# SCH_Forhorse_acw02_esphome_v2_2026-06-07.net
KiCad netlist of a schematic drawn in EasyEDA
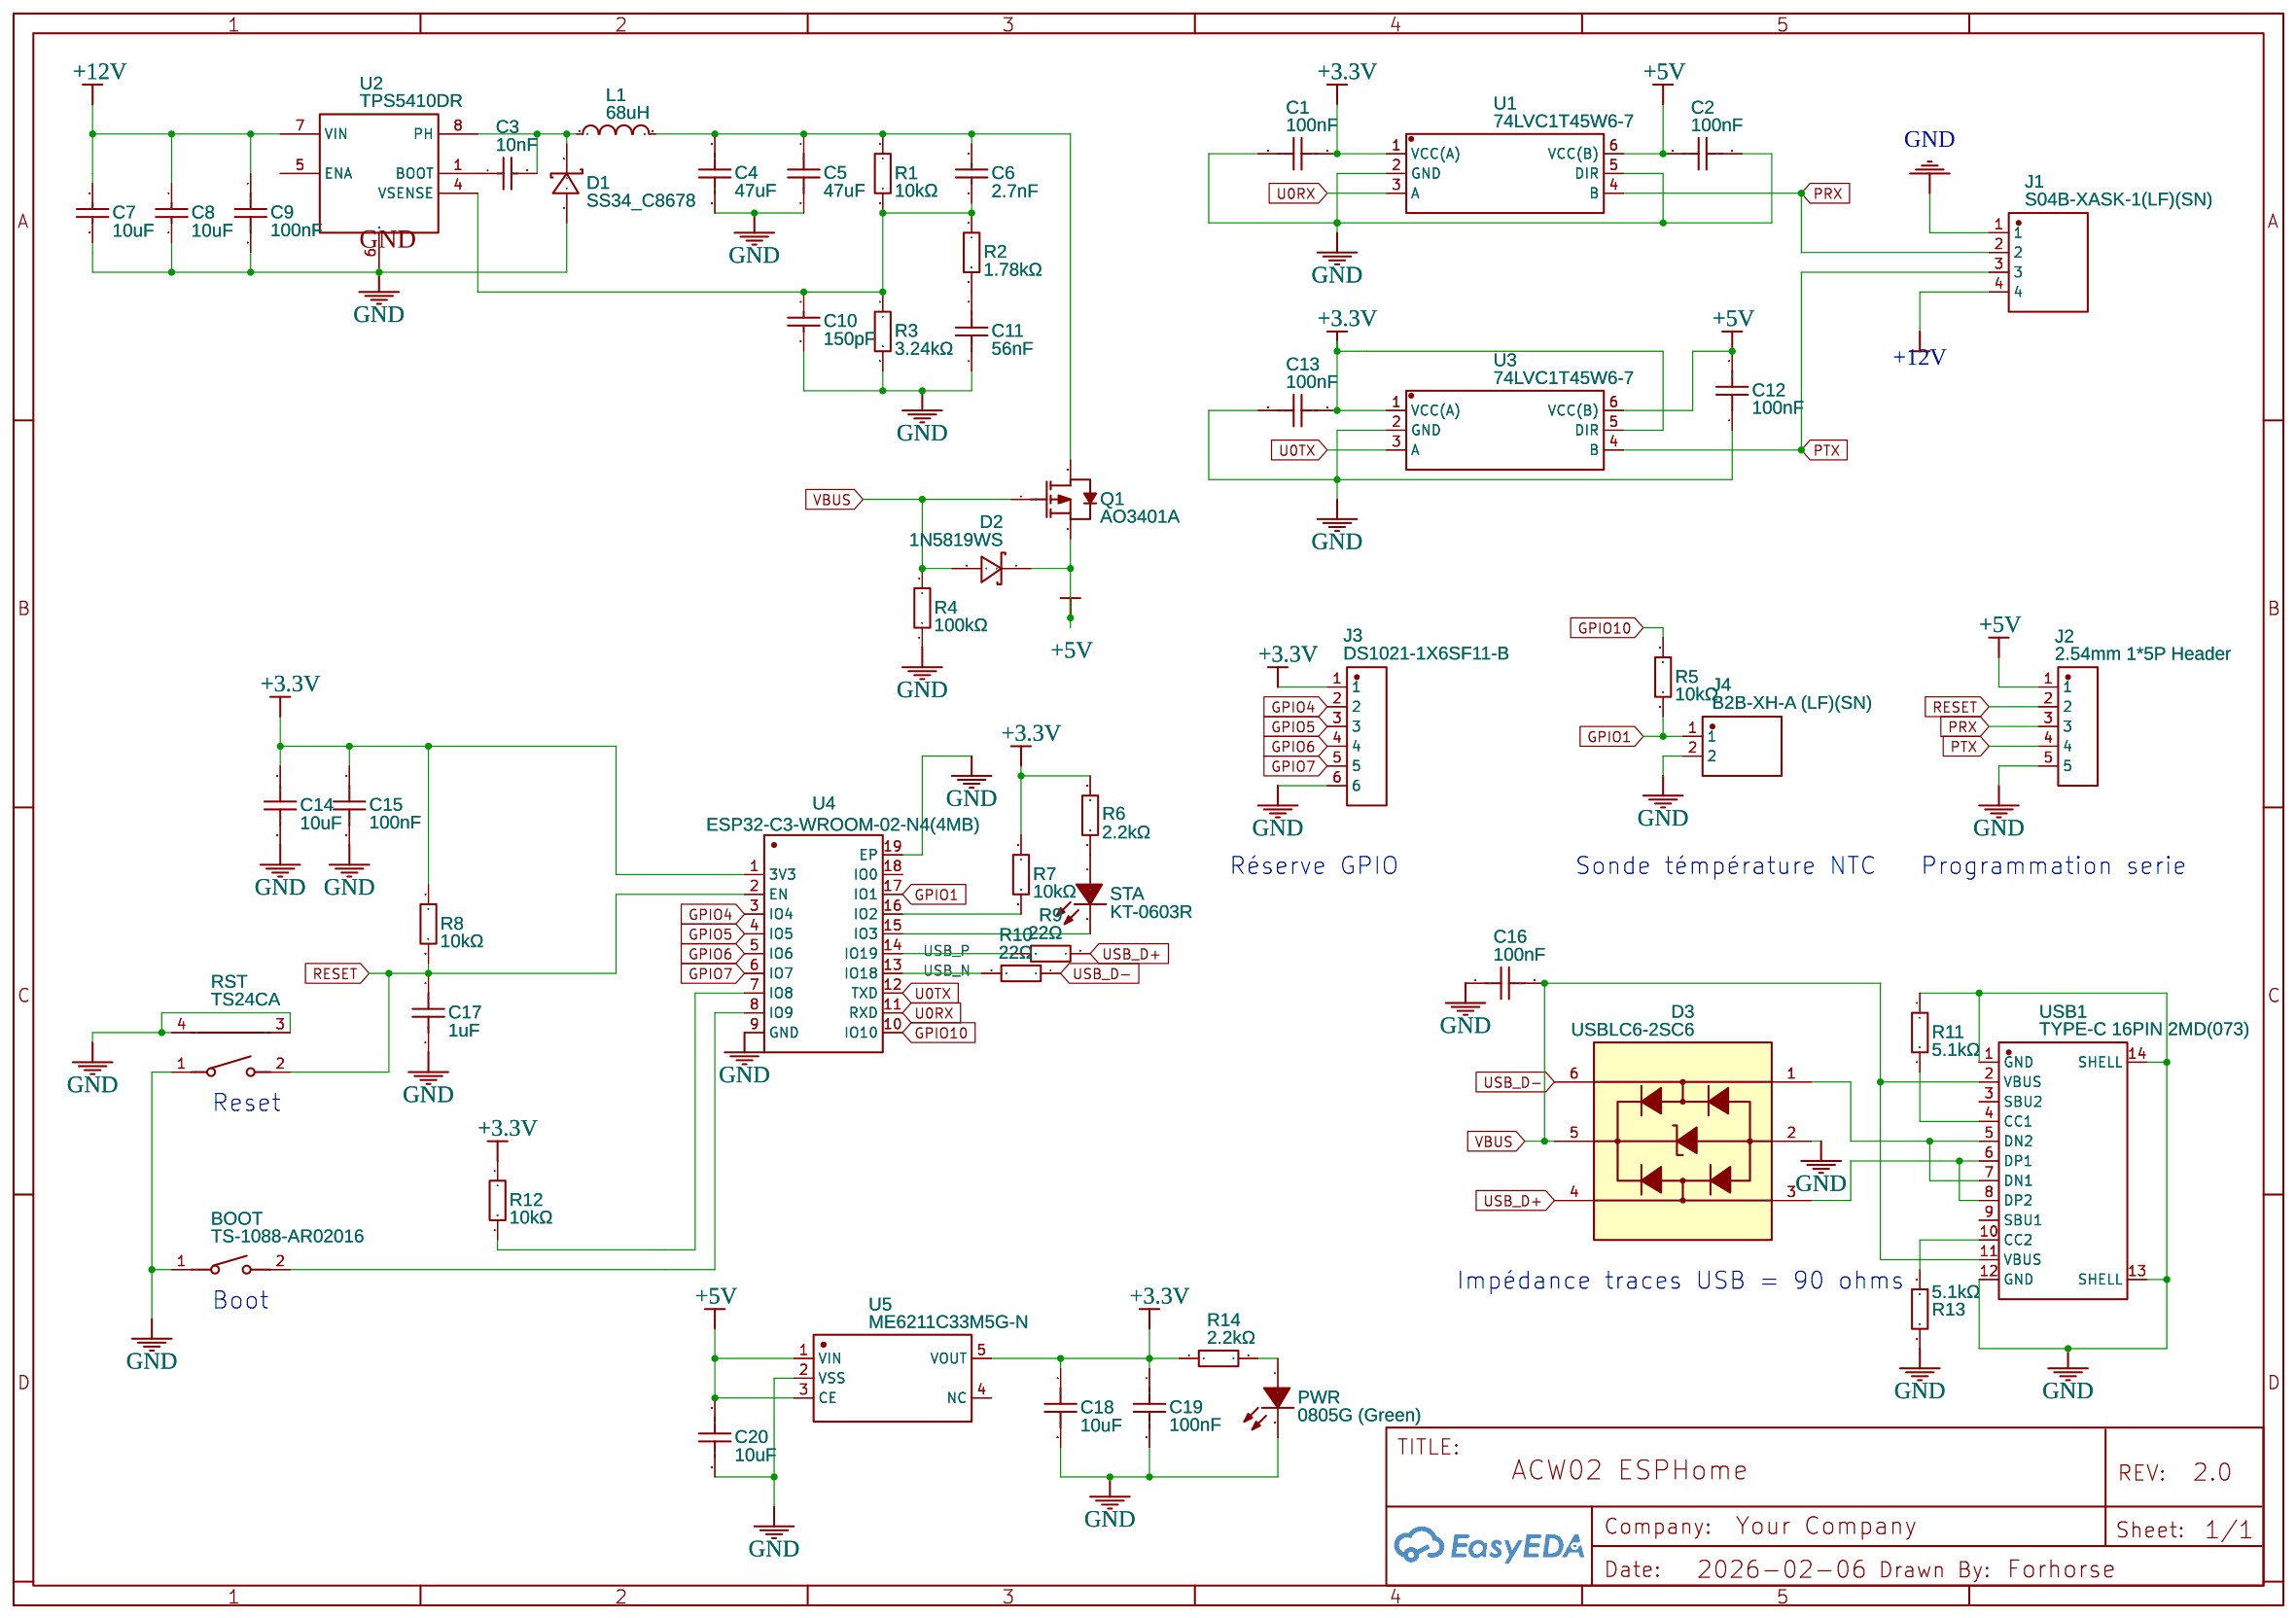
[diagram p0: schematic sheet]

(export (version "E")
  (design (tool "Eeschema 10.0.6"))
  (components
    (comp (ref "BOOT")
      (value "TS-1088-AR02016")
      (fields (field (name "Manufacturer") "XUNPU(讯普)"))
      (libsource (lib "") (part "TS-1088-AR02016"))
    )
    (comp (ref "C1")
      (value "100nF")
      (fields
        (field (name "Manufacturer Part") "CL05B104KO5NNNC")
        (field (name "Manufacturer") "SAMSUNG(三星)")
      )
      (libsource (lib "") (part "CL05B104KO5NNNC_1"))
    )
    (comp (ref "C2")
      (value "100nF")
      (fields
        (field (name "Manufacturer Part") "CL05B104KO5NNNC")
        (field (name "Manufacturer") "SAMSUNG(三星)")
      )
      (libsource (lib "") (part "CL05B104KO5NNNC_1"))
    )
    (comp (ref "C3")
      (value "10nF")
      (fields (field (name "Manufacturer Part") "0603B103K500NT") (field (name "Manufacturer") "FH(风华)"))
      (libsource (lib "") (part "0603B103K500NT"))
    )
    (comp (ref "C4")
      (value "47uF")
      (fields
        (field (name "Manufacturer Part") "CL31A476MPHNNNE")
        (field (name "Manufacturer") "SAMSUNG(三星)")
      )
      (libsource (lib "") (part "CL31A476MPHNNNE"))
    )
    (comp (ref "C5")
      (value "47uF")
      (fields
        (field (name "Manufacturer Part") "CL31A476MPHNNNE")
        (field (name "Manufacturer") "SAMSUNG(三星)")
      )
      (libsource (lib "") (part "CL31A476MPHNNNE"))
    )
    (comp (ref "C6")
      (value "2.7nF")
      (fields
        (field (name "Manufacturer Part") "GRM1885C1H272JA01D")
        (field (name "Manufacturer") "muRata(村田)")
      )
      (libsource (lib "") (part "GRM1885C1H272JA01D"))
    )
    (comp (ref "C7")
      (value "10uF")
      (fields
        (field (name "Manufacturer Part") "CL31A106KBHNNNE")
        (field (name "Manufacturer") "SAMSUNG(三星)")
      )
      (libsource (lib "") (part "CL31A106KBHNNNE"))
    )
    (comp (ref "C8")
      (value "10uF")
      (fields
        (field (name "Manufacturer Part") "CL31A106KBHNNNE")
        (field (name "Manufacturer") "SAMSUNG(三星)")
      )
      (libsource (lib "") (part "CL31A106KBHNNNE"))
    )
    (comp (ref "C9")
      (value "100nF")
      (fields
        (field (name "Manufacturer Part") "CL05B104KB54PNC")
        (field (name "Manufacturer") "SAMSUNG(三星)")
      )
      (libsource (lib "") (part "CL05B104KB54PNC"))
    )
    (comp (ref "C10")
      (value "150pF")
      (fields (field (name "Manufacturer Part") "0603B151K500NT") (field (name "Manufacturer") "FH(风华)"))
      (libsource (lib "") (part "0603B151K500NT"))
    )
    (comp (ref "C11")
      (value "56nF")
      (fields
        (field (name "Manufacturer Part") "CC0603KRX7R9BB563")
        (field (name "Manufacturer") "YAGEO(国巨)")
      )
      (libsource (lib "") (part "CC0603KRX7R9BB563"))
    )
    (comp (ref "C12")
      (value "100nF")
      (fields
        (field (name "Manufacturer Part") "CL05B104KO5NNNC")
        (field (name "Manufacturer") "SAMSUNG(三星)")
      )
      (libsource (lib "") (part "CL05B104KO5NNNC_2"))
    )
    (comp (ref "C13")
      (value "100nF")
      (fields
        (field (name "Manufacturer Part") "CL05B104KO5NNNC")
        (field (name "Manufacturer") "SAMSUNG(三星)")
      )
      (libsource (lib "") (part "CL05B104KO5NNNC_1"))
    )
    (comp (ref "C14")
      (value "10uF")
      (fields
        (field (name "Manufacturer Part") "CL10A106KP8NNNC")
        (field (name "Manufacturer") "SAMSUNG(三星)")
      )
      (libsource (lib "") (part "CL10A106KP8NNNC"))
    )
    (comp (ref "C15")
      (value "100nF")
      (fields
        (field (name "Manufacturer Part") "CL05B104KO5NNNC")
        (field (name "Manufacturer") "SAMSUNG(三星)")
      )
      (libsource (lib "") (part "CL05B104KO5NNNC"))
    )
    (comp (ref "C16")
      (value "100nF")
      (fields
        (field (name "Manufacturer Part") "CL05B104KO5NNNC")
        (field (name "Manufacturer") "SAMSUNG(三星)")
      )
      (libsource (lib "") (part "CL05B104KO5NNNC_3"))
    )
    (comp (ref "C17")
      (value "1uF")
      (fields
        (field (name "Manufacturer Part") "CL10A105KB8NNNC")
        (field (name "Manufacturer") "SAMSUNG(三星)")
      )
      (libsource (lib "") (part "CL10A105KB8NNNC"))
    )
    (comp (ref "C18")
      (value "10uF")
      (fields
        (field (name "Manufacturer Part") "CL10A106KP8NNNC")
        (field (name "Manufacturer") "SAMSUNG(三星)")
      )
      (libsource (lib "") (part "CL10A106KP8NNNC"))
    )
    (comp (ref "C19")
      (value "100nF")
      (fields
        (field (name "Manufacturer Part") "CL05B104KO5NNNC")
        (field (name "Manufacturer") "SAMSUNG(三星)")
      )
      (libsource (lib "") (part "CL05B104KO5NNNC"))
    )
    (comp (ref "C20")
      (value "10uF")
      (fields
        (field (name "Manufacturer Part") "CL10A106KP8NNNC")
        (field (name "Manufacturer") "SAMSUNG(三星)")
      )
      (libsource (lib "") (part "CL10A106KP8NNNC"))
    )
    (comp (ref "D1")
      (value "SS34_C8678")
      (fields (field (name "Manufacturer Part") "SS34") (field (name "Manufacturer") "MDD(辰达半导体)"))
      (libsource (lib "") (part "SS34_C8678"))
    )
    (comp (ref "D2")
      (value "1N5819WS")
      (fields (field (name "Manufacturer") "Hottech(合科泰)"))
      (libsource (lib "") (part "1N5819WS"))
    )
    (comp (ref "D3")
      (value "USBLC6-2SC6")
      (fields (field (name "Manufacturer") "ST(意法半导体)"))
      (libsource (lib "") (part "USBLC6-2SC6"))
    )
    (comp (ref "J1")
      (value "S04B-XASK-1(LF)(SN)")
      (fields (field (name "Manufacturer") "JST"))
      (libsource (lib "") (part "S04B-XASK-1(LF)(SN)"))
    )
    (comp (ref "J2")
      (value "2.54mm 1*5P Header")
      (fields (field (name "Manufacturer") "ReliaPro"))
      (libsource (lib "") (part "2.54mm 1*5P Header"))
    )
    (comp (ref "J3")
      (value "DS1021-1X6SF11-B")
      (fields (field (name "Manufacturer Part") "DS1021-1x6SF11-B") (field (name "Manufacturer") "CONNFLY"))
      (libsource (lib "") (part "DS1021-1X6SF11-B"))
    )
    (comp (ref "J4")
      (value "B2B-XH-A (LF)(SN)")
      (fields (field (name "Manufacturer Part") "B2B-XH-A(LF)(SN)") (field (name "Manufacturer") "JST"))
      (libsource (lib "") (part "B2B-XH-A (LF)(SN)"))
    )
    (comp (ref "L1")
      (value "68uH")
      (fields (field (name "Manufacturer Part") "FNR4030S680MT") (field (name "Manufacturer") "cjiang(长江微电)"))
      (libsource (lib "") (part "FNR4030S680MT"))
    )
    (comp (ref "PWR")
      (value "0805G (Green)")
      (fields (field (name "Manufacturer Part") "KT-0805G") (field (name "Manufacturer") "KENTO"))
      (libsource (lib "") (part "0805G (Green)"))
    )
    (comp (ref "Q1")
      (value "AO3401A")
      (fields (field (name "Manufacturer") "AOS"))
      (libsource (lib "") (part "AO3401A"))
    )
    (comp (ref "R1")
      (value "10kΩ")
      (fields
        (field (name "Manufacturer Part") "0603WAF1002T5E")
        (field (name "Manufacturer") "UNI-ROYAL(厚声)")
      )
      (libsource (lib "") (part "0603WAF1002T5E"))
    )
    (comp (ref "R2")
      (value "1.78kΩ")
      (fields
        (field (name "Manufacturer Part") "0603WAF1781T5E")
        (field (name "Manufacturer") "UNI-ROYAL(厚声)")
      )
      (libsource (lib "") (part "0603WAF1781T5E"))
    )
    (comp (ref "R3")
      (value "3.24kΩ")
      (fields
        (field (name "Manufacturer Part") "0603WAF3241T5E")
        (field (name "Manufacturer") "UNI-ROYAL(厚声)")
      )
      (libsource (lib "") (part "0603WAF3241T5E"))
    )
    (comp (ref "R4")
      (value "100kΩ")
      (fields
        (field (name "Manufacturer Part") "0603WAF1003T5E")
        (field (name "Manufacturer") "UNI-ROYAL(厚声)")
      )
      (libsource (lib "") (part "0603WAF1003T5E"))
    )
    (comp (ref "R5")
      (value "10kΩ")
      (fields
        (field (name "Manufacturer Part") "0603WAF1002T5E")
        (field (name "Manufacturer") "UNI-ROYAL(厚声)")
      )
      (libsource (lib "") (part "0603WAF1002T5E"))
    )
    (comp (ref "R6")
      (value "2.2kΩ")
      (fields
        (field (name "Manufacturer Part") "0603WAF2201T5E")
        (field (name "Manufacturer") "UNI-ROYAL(厚声)")
      )
      (libsource (lib "") (part "0603WAF2201T5E"))
    )
    (comp (ref "R7")
      (value "10kΩ")
      (fields
        (field (name "Manufacturer Part") "0603WAF1002T5E")
        (field (name "Manufacturer") "UNI-ROYAL(厚声)")
      )
      (libsource (lib "") (part "0603WAF1002T5E"))
    )
    (comp (ref "R8")
      (value "10kΩ")
      (fields
        (field (name "Manufacturer Part") "0603WAF1002T5E")
        (field (name "Manufacturer") "UNI-ROYAL(厚声)")
      )
      (libsource (lib "") (part "0603WAF1002T5E"))
    )
    (comp (ref "R9")
      (value "22Ω")
      (fields
        (field (name "Manufacturer Part") "0603WAF220JT5E")
        (field (name "Manufacturer") "UNI-ROYAL(厚声)")
      )
      (libsource (lib "") (part "0603WAF220JT5E"))
    )
    (comp (ref "R10")
      (value "22Ω")
      (fields
        (field (name "Manufacturer Part") "0603WAF220JT5E")
        (field (name "Manufacturer") "UNI-ROYAL(厚声)")
      )
      (libsource (lib "") (part "0603WAF220JT5E"))
    )
    (comp (ref "R11")
      (value "5.1kΩ")
      (fields
        (field (name "Manufacturer Part") "0603WAF5101T5E")
        (field (name "Manufacturer") "UNI-ROYAL(厚声)")
      )
      (libsource (lib "") (part "0603WAF5101T5E"))
    )
    (comp (ref "R12")
      (value "10kΩ")
      (fields
        (field (name "Manufacturer Part") "0603WAF1002T5E")
        (field (name "Manufacturer") "UNI-ROYAL(厚声)")
      )
      (libsource (lib "") (part "0603WAF1002T5E"))
    )
    (comp (ref "R13")
      (value "5.1kΩ")
      (fields
        (field (name "Manufacturer Part") "0603WAF5101T5E")
        (field (name "Manufacturer") "UNI-ROYAL(厚声)")
      )
      (libsource (lib "") (part "0603WAF5101T5E"))
    )
    (comp (ref "R14")
      (value "2.2kΩ")
      (fields
        (field (name "Manufacturer Part") "0603WAF2201T5E")
        (field (name "Manufacturer") "UNI-ROYAL(厚声)")
      )
      (libsource (lib "") (part "0603WAF2201T5E_1"))
    )
    (comp (ref "RST")
      (value "TS24CA")
      (fields (field (name "Manufacturer") "SHOU HAN(首韩)"))
      (libsource (lib "") (part "TS24CA"))
    )
    (comp (ref "STA")
      (value "KT-0603R")
      (fields (field (name "Manufacturer") "KENTO"))
      (libsource (lib "") (part "KT-0603R"))
    )
    (comp (ref "U1")
      (value "74LVC1T45W6-7")
      (fields (field (name "Manufacturer") "DIODES(美台)"))
      (libsource (lib "") (part "74LVC1T45W6-7"))
    )
    (comp (ref "U2")
      (value "TPS5410DR")
      (fields (field (name "Manufacturer") "TI(德州仪器)"))
      (libsource (lib "") (part "TPS5410DR"))
    )
    (comp (ref "U3")
      (value "74LVC1T45W6-7")
      (fields (field (name "Manufacturer") "DIODES(美台)"))
      (libsource (lib "") (part "74LVC1T45W6-7"))
    )
    (comp (ref "U4")
      (value "ESP32-C3-WROOM-02-N4(4MB)")
      (fields
        (field (name "Manufacturer Part") "ESP32-C3-WROOM-02-N4")
        (field (name "Manufacturer") "ESPRESSIF(乐鑫)")
      )
      (libsource (lib "") (part "ESP32-C3-WROOM-02-N4(4MB)"))
    )
    (comp (ref "U5")
      (value "ME6211C33M5G-N")
      (fields (field (name "Manufacturer") "MICRONE(南京微盟)"))
      (libsource (lib "") (part "ME6211C33M5G-N"))
    )
    (comp (ref "USB1")
      (value "TYPE-C 16PIN 2MD(073)")
      (fields (field (name "Manufacturer") "SHOU HAN(首韩)"))
      (libsource (lib "") (part "TYPE-C 16PIN 2MD(073)"))
    )
  )
  (nets
    (net (code "1") (name "+3.3V") (class "Default")
      (node (ref "C1") (pin "1") (pinfunction "1_1") (pintype "unspecified"))
      (node (ref "C13") (pin "1") (pinfunction "1_1") (pintype "unspecified"))
      (node (ref "C14") (pin "1") (pinfunction "1_1") (pintype "unspecified"))
      (node (ref "C15") (pin "1") (pinfunction "1_1") (pintype "unspecified"))
      (node (ref "C18") (pin "1") (pinfunction "1_1") (pintype "unspecified"))
      (node (ref "C19") (pin "1") (pinfunction "1_1") (pintype "unspecified"))
      (node (ref "J3") (pin "1") (pinfunction "1_1") (pintype "unspecified"))
      (node (ref "R12") (pin "1") (pinfunction "1_1") (pintype "input"))
      (node (ref "R14") (pin "1") (pinfunction "1_1") (pintype "input"))
      (node (ref "R6") (pin "2") (pinfunction "2_2") (pintype "input"))
      (node (ref "R7") (pin "1") (pinfunction "1_1") (pintype "input"))
      (node (ref "R8") (pin "1") (pinfunction "1_1") (pintype "input"))
      (node (ref "U1") (pin "1") (pinfunction "VCC(A)_1") (pintype "unspecified"))
      (node (ref "U3") (pin "1") (pinfunction "VCC(A)_1") (pintype "unspecified"))
      (node (ref "U3") (pin "5") (pinfunction "DIR_5") (pintype "unspecified"))
      (node (ref "U4") (pin "1") (pinfunction "3V3_1") (pintype "unspecified"))
      (node (ref "U5") (pin "5") (pinfunction "VOUT_5") (pintype "unspecified"))
    )
    (net (code "2") (name "+5V") (class "Default")
      (node (ref "C12") (pin "2") (pinfunction "2_2") (pintype "unspecified"))
      (node (ref "C2") (pin "2") (pinfunction "2_2") (pintype "unspecified"))
      (node (ref "C20") (pin "1") (pinfunction "1_1") (pintype "unspecified"))
      (node (ref "D2") (pin "1") (pinfunction "K_1") (pintype "unspecified"))
      (node (ref "J2") (pin "1") (pinfunction "1_1") (pintype "unspecified"))
      (node (ref "Q1") (pin "2") (pinfunction "S_2") (pintype "unspecified"))
      (node (ref "U1") (pin "6") (pinfunction "VCC(B)_6") (pintype "unspecified"))
      (node (ref "U3") (pin "6") (pinfunction "VCC(B)_6") (pintype "unspecified"))
      (node (ref "U5") (pin "1") (pinfunction "VIN_1") (pintype "unspecified"))
      (node (ref "U5") (pin "3") (pinfunction "CE_3") (pintype "unspecified"))
    )
    (net (code "3") (name "+12V") (class "Default")
      (node (ref "C7") (pin "1") (pinfunction "1_1") (pintype "input"))
      (node (ref "C8") (pin "1") (pinfunction "1_1") (pintype "input"))
      (node (ref "C9") (pin "1") (pinfunction "1_1") (pintype "unspecified"))
      (node (ref "J1") (pin "4") (pinfunction "4_4") (pintype "unspecified"))
      (node (ref "U2") (pin "7") (pinfunction "VIN_7") (pintype "passive"))
    )
    (net (code "4") (name "/USB_N") (class "Default")
      (node (ref "R10") (pin "2") (pinfunction "2_2") (pintype "input"))
      (node (ref "U4") (pin "13") (pinfunction "IO18_13") (pintype "unspecified"))
    )
    (net (code "5") (name "/USB_P") (class "Default")
      (node (ref "R9") (pin "2") (pinfunction "2_2") (pintype "input"))
      (node (ref "U4") (pin "14") (pinfunction "IO19_14") (pintype "unspecified"))
    )
    (net (code "6") (name "GND") (class "Default")
      (node (ref "BOOT") (pin "1") (pinfunction "1_1") (pintype "unspecified"))
      (node (ref "C1") (pin "2") (pinfunction "2_2") (pintype "unspecified"))
      (node (ref "C10") (pin "2") (pinfunction "2_2") (pintype "input"))
      (node (ref "C11") (pin "1") (pinfunction "1_1") (pintype "unspecified"))
      (node (ref "C12") (pin "1") (pinfunction "1_1") (pintype "unspecified"))
      (node (ref "C13") (pin "2") (pinfunction "2_2") (pintype "unspecified"))
      (node (ref "C14") (pin "2") (pinfunction "2_2") (pintype "unspecified"))
      (node (ref "C15") (pin "2") (pinfunction "2_2") (pintype "unspecified"))
      (node (ref "C16") (pin "1") (pinfunction "1_1") (pintype "unspecified"))
      (node (ref "C17") (pin "2") (pinfunction "2_2") (pintype "unspecified"))
      (node (ref "C18") (pin "2") (pinfunction "2_2") (pintype "unspecified"))
      (node (ref "C19") (pin "2") (pinfunction "2_2") (pintype "unspecified"))
      (node (ref "C2") (pin "1") (pinfunction "1_1") (pintype "unspecified"))
      (node (ref "C20") (pin "2") (pinfunction "2_2") (pintype "unspecified"))
      (node (ref "C4") (pin "2") (pinfunction "2_2") (pintype "unspecified"))
      (node (ref "C5") (pin "2") (pinfunction "2_2") (pintype "unspecified"))
      (node (ref "C7") (pin "2") (pinfunction "2_2") (pintype "input"))
      (node (ref "C8") (pin "2") (pinfunction "2_2") (pintype "input"))
      (node (ref "C9") (pin "2") (pinfunction "2_2") (pintype "unspecified"))
      (node (ref "D1") (pin "2") (pinfunction "A_2") (pintype "unspecified"))
      (node (ref "D3") (pin "2") (pinfunction "2_2") (pintype "input"))
      (node (ref "J1") (pin "1") (pinfunction "1_1") (pintype "unspecified"))
      (node (ref "J2") (pin "5") (pinfunction "5_5") (pintype "unspecified"))
      (node (ref "J3") (pin "6") (pinfunction "6_6") (pintype "unspecified"))
      (node (ref "J4") (pin "2") (pinfunction "2_2") (pintype "unspecified"))
      (node (ref "PWR") (pin "2") (pinfunction "K_2") (pintype "unspecified"))
      (node (ref "R11") (pin "1") (pinfunction "1_1") (pintype "input"))
      (node (ref "R13") (pin "2") (pinfunction "2_2") (pintype "input"))
      (node (ref "R3") (pin "2") (pinfunction "2_2") (pintype "input"))
      (node (ref "R4") (pin "2") (pinfunction "2_2") (pintype "input"))
      (node (ref "RST") (pin "1") (pinfunction "1_1") (pintype "unspecified"))
      (node (ref "RST") (pin "3") (pinfunction "3_3") (pintype "unspecified"))
      (node (ref "RST") (pin "4") (pinfunction "4_4") (pintype "unspecified"))
      (node (ref "U1") (pin "2") (pinfunction "GND_2") (pintype "unspecified"))
      (node (ref "U1") (pin "5") (pinfunction "DIR_5") (pintype "unspecified"))
      (node (ref "U2") (pin "6") (pinfunction "GND_6") (pintype "passive"))
      (node (ref "U3") (pin "2") (pinfunction "GND_2") (pintype "unspecified"))
      (node (ref "U4") (pin "19") (pinfunction "EP_19") (pintype "unspecified"))
      (node (ref "U4") (pin "9") (pinfunction "GND_9") (pintype "unspecified"))
      (node (ref "U5") (pin "2") (pinfunction "VSS_2") (pintype "unspecified"))
      (node (ref "USB1") (pin "1") (pinfunction "GND_1") (pintype "unspecified"))
      (node (ref "USB1") (pin "12") (pinfunction "GND_12") (pintype "unspecified"))
      (node (ref "USB1") (pin "13") (pinfunction "SHELL_13") (pintype "unspecified"))
      (node (ref "USB1") (pin "14") (pinfunction "SHELL_14") (pintype "unspecified"))
    )
    (net (code "7") (name "GPIO1") (class "Default")
      (node (ref "J4") (pin "1") (pinfunction "1_1") (pintype "unspecified"))
      (node (ref "R5") (pin "2") (pinfunction "2_2") (pintype "input"))
      (node (ref "U4") (pin "17") (pinfunction "IO1_17") (pintype "unspecified"))
    )
    (net (code "8") (name "GPIO4") (class "Default")
      (node (ref "J3") (pin "2") (pinfunction "2_2") (pintype "unspecified"))
      (node (ref "U4") (pin "3") (pinfunction "IO4_3") (pintype "unspecified"))
    )
    (net (code "9") (name "GPIO5") (class "Default")
      (node (ref "J3") (pin "3") (pinfunction "3_3") (pintype "unspecified"))
      (node (ref "U4") (pin "4") (pinfunction "IO5_4") (pintype "unspecified"))
    )
    (net (code "10") (name "GPIO6") (class "Default")
      (node (ref "J3") (pin "4") (pinfunction "4_4") (pintype "unspecified"))
      (node (ref "U4") (pin "5") (pinfunction "IO6_5") (pintype "unspecified"))
    )
    (net (code "11") (name "GPIO7") (class "Default")
      (node (ref "J3") (pin "5") (pinfunction "5_5") (pintype "unspecified"))
      (node (ref "U4") (pin "6") (pinfunction "IO7_6") (pintype "unspecified"))
    )
    (net (code "12") (name "GPIO10") (class "Default")
      (node (ref "R5") (pin "1") (pinfunction "1_1") (pintype "input"))
      (node (ref "U4") (pin "10") (pinfunction "IO10_10") (pintype "unspecified"))
    )
    (net (code "13") (name "Net-(C11-Pad2)") (class "Default")
      (node (ref "C11") (pin "2") (pinfunction "2_2") (pintype "unspecified"))
      (node (ref "R2") (pin "2") (pinfunction "2_2") (pintype "input"))
    )
    (net (code "14") (name "Net-(D1-K)") (class "Default")
      (node (ref "C3") (pin "2") (pinfunction "2_2") (pintype "input"))
      (node (ref "D1") (pin "1") (pinfunction "K_1") (pintype "unspecified"))
      (node (ref "L1") (pin "1") (pinfunction "1_1") (pintype "unspecified"))
      (node (ref "U2") (pin "8") (pinfunction "PH_8") (pintype "passive"))
    )
    (net (code "15") (name "Net-(PWR-A)") (class "Default")
      (node (ref "PWR") (pin "1") (pinfunction "A_1") (pintype "unspecified"))
      (node (ref "R14") (pin "2") (pinfunction "2_2") (pintype "input"))
    )
    (net (code "16") (name "Net-(Q1-D)") (class "Default")
      (node (ref "C4") (pin "1") (pinfunction "1_1") (pintype "unspecified"))
      (node (ref "C5") (pin "1") (pinfunction "1_1") (pintype "unspecified"))
      (node (ref "C6") (pin "1") (pinfunction "1_1") (pintype "input"))
      (node (ref "L1") (pin "2") (pinfunction "2_2") (pintype "unspecified"))
      (node (ref "Q1") (pin "3") (pinfunction "D_3") (pintype "unspecified"))
      (node (ref "R1") (pin "1") (pinfunction "1_1") (pintype "input"))
    )
    (net (code "17") (name "Net-(STA-A)") (class "Default")
      (node (ref "R6") (pin "1") (pinfunction "1_1") (pintype "input"))
      (node (ref "STA") (pin "2") (pinfunction "A_2") (pintype "unspecified"))
    )
    (net (code "18") (name "Net-(STA-K)") (class "Default")
      (node (ref "STA") (pin "1") (pinfunction "K_1") (pintype "unspecified"))
      (node (ref "U4") (pin "15") (pinfunction "IO3_15") (pintype "unspecified"))
    )
    (net (code "19") (name "Net-(U2-BOOT)") (class "Default")
      (node (ref "C3") (pin "1") (pinfunction "1_1") (pintype "input"))
      (node (ref "U2") (pin "1") (pinfunction "BOOT_1") (pintype "unspecified"))
    )
    (net (code "20") (name "Net-(U2-VSENSE)") (class "Default")
      (node (ref "C10") (pin "1") (pinfunction "1_1") (pintype "input"))
      (node (ref "C6") (pin "2") (pinfunction "2_2") (pintype "input"))
      (node (ref "R1") (pin "2") (pinfunction "2_2") (pintype "input"))
      (node (ref "R2") (pin "1") (pinfunction "1_1") (pintype "input"))
      (node (ref "R3") (pin "1") (pinfunction "1_1") (pintype "input"))
      (node (ref "U2") (pin "4") (pinfunction "VSENSE_4") (pintype "unspecified"))
    )
    (net (code "21") (name "Net-(U4-IO2)") (class "Default")
      (node (ref "R7") (pin "2") (pinfunction "2_2") (pintype "input"))
      (node (ref "U4") (pin "16") (pinfunction "IO2_16") (pintype "unspecified"))
    )
    (net (code "22") (name "Net-(U4-IO8)") (class "Default")
      (node (ref "R12") (pin "2") (pinfunction "2_2") (pintype "input"))
      (node (ref "U4") (pin "7") (pinfunction "IO8_7") (pintype "unspecified"))
    )
    (net (code "23") (name "Net-(U4-IO9)") (class "Default")
      (node (ref "BOOT") (pin "2") (pinfunction "2_2") (pintype "unspecified"))
      (node (ref "U4") (pin "8") (pinfunction "IO9_8") (pintype "unspecified"))
    )
    (net (code "24") (name "Net-(USB1-CC1)") (class "Default")
      (node (ref "R11") (pin "2") (pinfunction "2_2") (pintype "input"))
      (node (ref "USB1") (pin "4") (pinfunction "CC1_4") (pintype "unspecified"))
    )
    (net (code "25") (name "Net-(USB1-CC2)") (class "Default")
      (node (ref "R13") (pin "1") (pinfunction "1_1") (pintype "input"))
      (node (ref "USB1") (pin "10") (pinfunction "CC2_10") (pintype "unspecified"))
    )
    (net (code "26") (name "Net-(USB1-DN1)") (class "Default")
      (node (ref "D3") (pin "1") (pinfunction "1_1") (pintype "input"))
      (node (ref "USB1") (pin "5") (pinfunction "DN2_5") (pintype "unspecified"))
      (node (ref "USB1") (pin "7") (pinfunction "DN1_7") (pintype "unspecified"))
    )
    (net (code "27") (name "Net-(USB1-DP1)") (class "Default")
      (node (ref "D3") (pin "3") (pinfunction "3_3") (pintype "input"))
      (node (ref "USB1") (pin "6") (pinfunction "DP1_6") (pintype "unspecified"))
      (node (ref "USB1") (pin "8") (pinfunction "DP2_8") (pintype "unspecified"))
    )
    (net (code "28") (name "PRX") (class "Default")
      (node (ref "J1") (pin "2") (pinfunction "2_2") (pintype "unspecified"))
      (node (ref "J2") (pin "3") (pinfunction "3_3") (pintype "unspecified"))
      (node (ref "U1") (pin "4") (pinfunction "B_4") (pintype "unspecified"))
    )
    (net (code "29") (name "PTX") (class "Default")
      (node (ref "J1") (pin "3") (pinfunction "3_3") (pintype "unspecified"))
      (node (ref "J2") (pin "4") (pinfunction "4_4") (pintype "unspecified"))
      (node (ref "U3") (pin "4") (pinfunction "B_4") (pintype "unspecified"))
    )
    (net (code "30") (name "RESET") (class "Default")
      (node (ref "C17") (pin "1") (pinfunction "1_1") (pintype "unspecified"))
      (node (ref "J2") (pin "2") (pinfunction "2_2") (pintype "unspecified"))
      (node (ref "R8") (pin "2") (pinfunction "2_2") (pintype "input"))
      (node (ref "RST") (pin "2") (pinfunction "2_2") (pintype "unspecified"))
      (node (ref "U4") (pin "2") (pinfunction "EN_2") (pintype "unspecified"))
    )
    (net (code "31") (name "U0RX") (class "Default")
      (node (ref "U1") (pin "3") (pinfunction "A_3") (pintype "unspecified"))
      (node (ref "U4") (pin "11") (pinfunction "RXD_11") (pintype "unspecified"))
    )
    (net (code "32") (name "U0TX") (class "Default")
      (node (ref "U3") (pin "3") (pinfunction "A_3") (pintype "unspecified"))
      (node (ref "U4") (pin "12") (pinfunction "TXD_12") (pintype "unspecified"))
    )
    (net (code "33") (name "USB_D+") (class "Default")
      (node (ref "D3") (pin "4") (pinfunction "4_4") (pintype "input"))
      (node (ref "R9") (pin "1") (pinfunction "1_1") (pintype "input"))
    )
    (net (code "34") (name "USB_D-") (class "Default")
      (node (ref "D3") (pin "6") (pinfunction "6_6") (pintype "input"))
      (node (ref "R10") (pin "1") (pinfunction "1_1") (pintype "input"))
    )
    (net (code "35") (name "VBUS") (class "Default")
      (node (ref "C16") (pin "2") (pinfunction "2_2") (pintype "unspecified"))
      (node (ref "D2") (pin "2") (pinfunction "A_2") (pintype "unspecified"))
      (node (ref "D3") (pin "5") (pinfunction "5_5") (pintype "input"))
      (node (ref "Q1") (pin "1") (pinfunction "G_1") (pintype "unspecified"))
      (node (ref "R4") (pin "1") (pinfunction "1_1") (pintype "input"))
      (node (ref "USB1") (pin "11") (pinfunction "VBUS_11") (pintype "unspecified"))
      (node (ref "USB1") (pin "2") (pinfunction "VBUS_2") (pintype "unspecified"))
    )
    (net (code "36") (name "unconnected-(U2-ENA-Pad5)") (class "Default")
      (node (ref "U2") (pin "5") (pinfunction "ENA_5") (pintype "unspecified"))
    )
    (net (code "37") (name "unconnected-(U4-IO0-Pad18)") (class "Default")
      (node (ref "U4") (pin "18") (pinfunction "IO0_18") (pintype "unspecified"))
    )
    (net (code "38") (name "unconnected-(U5-NC-Pad4)") (class "Default")
      (node (ref "U5") (pin "4") (pinfunction "NC_4") (pintype "unspecified"))
    )
    (net (code "39") (name "unconnected-(USB1-SBU1-Pad9)") (class "Default")
      (node (ref "USB1") (pin "9") (pinfunction "SBU1_9") (pintype "unspecified"))
    )
    (net (code "40") (name "unconnected-(USB1-SBU2-Pad3)") (class "Default")
      (node (ref "USB1") (pin "3") (pinfunction "SBU2_3") (pintype "unspecified"))
    )
  )
)
